# ETHERNET.net
KiCad netlist of a schematic drawn in Altium Designer
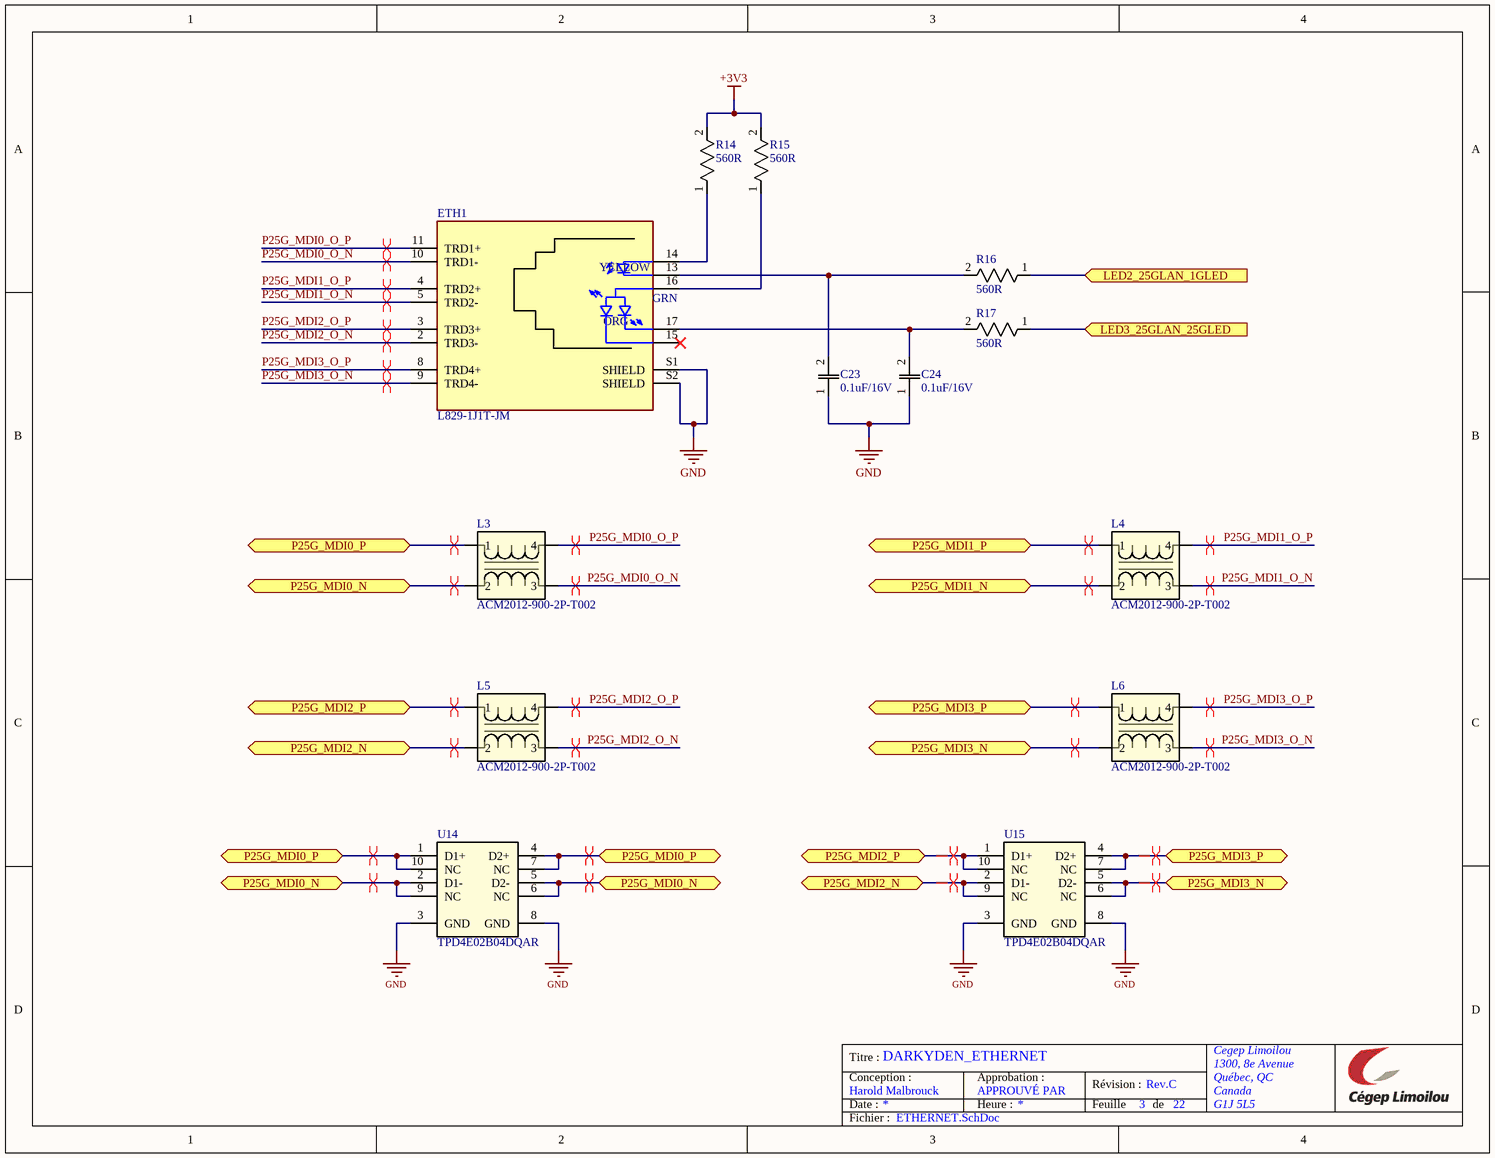
[diagram p0: ETHERNET.SchDoc]

(export (version "E")
  (design (tool "Eeschema 10.0.6"))
  (components
    (comp (ref "C23")
      (value "0.1uF/16V")
      (footprint "C0805")
      (description "0.1uF/16V ±10% X7R 0805 (2012METRIC) Ceramic Capacitor SMD Auto X7R")
      (fields
        (field (name "MANUFACTURER") "KEMET")
        (field (name "MANUFACTURER PART NUMBER") "C0805C104K4RACAUTO")
      )
      (libsource (lib "DARKYDEN") (part "C0805C104K4RACAUTO"))
    )
    (comp (ref "C24")
      (value "0.1uF/16V")
      (footprint "C0805")
      (description "0.1uF/16V ±10% X7R 0805 (2012METRIC) Ceramic Capacitor SMD Auto X7R")
      (fields
        (field (name "MANUFACTURER") "KEMET")
        (field (name "MANUFACTURER PART NUMBER") "C0805C104K4RACAUTO")
      )
      (libsource (lib "DARKYDEN") (part "C0805C104K4RACAUTO"))
    )
    (comp (ref "ETH1")
      (value "L829-1J1T-JM")
      (footprint "RJ-45")
      (description "Modular Connectors / Ethernet Connectors 1x1 2.5GBT MagJack")
      (fields
        (field (name "DIGI-KEY_PART_NUMBER") "507-2068-ND")
        (field (name "MF") "Bel Magnetic Solutions")
      )
      (libsource (lib "L829-1J1T-JM") (part "L829-1J1T-JM"))
    )
    (comp (ref "L3")
      (value "ACM2012-900-2P-T002")
      (footprint "SamacSys:ACM20129002PT002")
      (description "Ferrite Beads Wirewound Common Mode Filter 90Ohm 100MHz 400mA 0805 T/R")
      (fields (field (name "MOUSER PART NUMBER") "810-ACM20129002PT002") (field (name "MANUFACTURER") "TDK"))
      (libsource (lib "SamacSys") (part "ACM2012-900-2P-T002"))
    )
    (comp (ref "L4")
      (value "ACM2012-900-2P-T002")
      (footprint "SamacSys:ACM20129002PT002")
      (description "Ferrite Beads Wirewound Common Mode Filter 90Ohm 100MHz 400mA 0805 T/R")
      (fields (field (name "MOUSER PART NUMBER") "810-ACM20129002PT002") (field (name "MANUFACTURER") "TDK"))
      (libsource (lib "SamacSys") (part "ACM2012-900-2P-T002"))
    )
    (comp (ref "L5")
      (value "ACM2012-900-2P-T002")
      (footprint "SamacSys:ACM20129002PT002")
      (description "Ferrite Beads Wirewound Common Mode Filter 90Ohm 100MHz 400mA 0805 T/R")
      (fields (field (name "MOUSER PART NUMBER") "810-ACM20129002PT002") (field (name "MANUFACTURER") "TDK"))
      (libsource (lib "SamacSys") (part "ACM2012-900-2P-T002"))
    )
    (comp (ref "L6")
      (value "ACM2012-900-2P-T002")
      (footprint "SamacSys:ACM20129002PT002")
      (description "Ferrite Beads Wirewound Common Mode Filter 90Ohm 100MHz 400mA 0805 T/R")
      (fields (field (name "MOUSER PART NUMBER") "810-ACM20129002PT002") (field (name "MANUFACTURER") "TDK"))
      (libsource (lib "SamacSys") (part "ACM2012-900-2P-T002"))
    )
    (comp (ref "R14")
      (value "560R")
      (footprint "RESC1608X55N")
      (description "560 Ohm, ï¿½ 1%, 100 mW, 0603 [1608 Metric], Thick Film, Precision")
      (fields
        (field (name "MANUFACTURER") "Panasonic")
        (field (name "MANUFACTURER PART NUMBER") "ERJ-3EKF5600V")
      )
      (libsource (lib "DARKYDEN") (part "ERJ-3EKF5600V"))
    )
    (comp (ref "R15")
      (value "560R")
      (footprint "RESC1608X55N")
      (description "560 Ohm, ï¿½ 1%, 100 mW, 0603 [1608 Metric], Thick Film, Precision")
      (fields
        (field (name "MANUFACTURER") "Panasonic")
        (field (name "MANUFACTURER PART NUMBER") "ERJ-3EKF5600V")
      )
      (libsource (lib "DARKYDEN") (part "ERJ-3EKF5600V"))
    )
    (comp (ref "R16")
      (value "560R")
      (footprint "RESC1608X55N")
      (description "560 Ohm, ï¿½ 1%, 100 mW, 0603 [1608 Metric], Thick Film, Precision")
      (fields
        (field (name "MANUFACTURER") "Panasonic")
        (field (name "MANUFACTURER PART NUMBER") "ERJ-3EKF5600V")
      )
      (libsource (lib "DARKYDEN") (part "ERJ-3EKF5600V"))
    )
    (comp (ref "R17")
      (value "560R")
      (footprint "RESC1608X55N")
      (description "560 Ohm, ï¿½ 1%, 100 mW, 0603 [1608 Metric], Thick Film, Precision")
      (fields
        (field (name "MANUFACTURER") "Panasonic")
        (field (name "MANUFACTURER PART NUMBER") "ERJ-3EKF5600V")
      )
      (libsource (lib "DARKYDEN") (part "ERJ-3EKF5600V"))
    )
    (comp (ref "U14")
      (value "TPD4E02B04DQAR")
      (footprint "DQA0010A")
      (description "TVS DIODE 3.6V 8.8V 10USON / 4-Channel ESD Protection Diode for USB Type-C and HDMI 2.0")
      (fields (field (name "MANUFACTURER") "Texas Instruments"))
      (libsource (lib "TPD4E02B04DQAR") (part "TPD4E02B04DQAR"))
    )
    (comp (ref "U15")
      (value "TPD4E02B04DQAR")
      (footprint "DQA0010A")
      (description "TVS DIODE 3.6V 8.8V 10USON / 4-Channel ESD Protection Diode for USB Type-C and HDMI 2.0")
      (fields (field (name "MANUFACTURER") "Texas Instruments"))
      (libsource (lib "TPD4E02B04DQAR") (part "TPD4E02B04DQAR"))
    )
  )
  (nets
    (net (code "1") (name "+3V3") (class "Default")
      (node (ref "R14") (pin "2") (pinfunction "2_2") (pintype "passive"))
      (node (ref "R15") (pin "2") (pinfunction "2_2") (pintype "passive"))
    )
    (net (code "2") (name "/LED2_25GLAN_1GLED") (class "Default")
      (node (ref "R16") (pin "1") (pinfunction "1_1") (pintype "passive"))
    )
    (net (code "3") (name "/LED3_25GLAN_25GLED") (class "Default")
      (node (ref "R17") (pin "1") (pinfunction "1_1") (pintype "passive"))
    )
    (net (code "4") (name "/P25G_MDI0_N") (class "Default")
      (node (ref "L3") (pin "2") (pinfunction "2_2") (pintype "passive"))
      (node (ref "U14") (pin "2") (pinfunction "D1-_2") (pintype "passive"))
      (node (ref "U14") (pin "5") (pinfunction "D2-_5") (pintype "passive"))
      (node (ref "U14") (pin "6") (pinfunction "NC_6") (pintype "passive"))
      (node (ref "U14") (pin "9") (pinfunction "NC_9") (pintype "passive"))
    )
    (net (code "5") (name "/P25G_MDI0_O_N") (class "Default")
      (node (ref "ETH1") (pin "10") (pinfunction "TRD1-_10") (pintype "passive"))
      (node (ref "L3") (pin "3") (pinfunction "3_3") (pintype "passive"))
    )
    (net (code "6") (name "/P25G_MDI0_O_P") (class "Default")
      (node (ref "ETH1") (pin "11") (pinfunction "TRD1+_11") (pintype "passive"))
      (node (ref "L3") (pin "4") (pinfunction "4_4") (pintype "passive"))
    )
    (net (code "7") (name "/P25G_MDI0_P") (class "Default")
      (node (ref "L3") (pin "1") (pinfunction "1_1") (pintype "passive"))
      (node (ref "U14") (pin "1") (pinfunction "D1+_1") (pintype "passive"))
      (node (ref "U14") (pin "10") (pinfunction "NC_10") (pintype "passive"))
      (node (ref "U14") (pin "4") (pinfunction "D2+_4") (pintype "passive"))
      (node (ref "U14") (pin "7") (pinfunction "NC_7") (pintype "passive"))
    )
    (net (code "8") (name "/P25G_MDI1_N") (class "Default")
      (node (ref "L4") (pin "2") (pinfunction "2_2") (pintype "passive"))
    )
    (net (code "9") (name "/P25G_MDI1_O_N") (class "Default")
      (node (ref "ETH1") (pin "5") (pinfunction "TRD2-_5") (pintype "passive"))
      (node (ref "L4") (pin "3") (pinfunction "3_3") (pintype "passive"))
    )
    (net (code "10") (name "/P25G_MDI1_O_P") (class "Default")
      (node (ref "ETH1") (pin "4") (pinfunction "TRD2+_4") (pintype "passive"))
      (node (ref "L4") (pin "4") (pinfunction "4_4") (pintype "passive"))
    )
    (net (code "11") (name "/P25G_MDI1_P") (class "Default")
      (node (ref "L4") (pin "1") (pinfunction "1_1") (pintype "passive"))
    )
    (net (code "12") (name "/P25G_MDI2_N") (class "Default")
      (node (ref "L5") (pin "2") (pinfunction "2_2") (pintype "passive"))
      (node (ref "U15") (pin "2") (pinfunction "D1-_2") (pintype "passive"))
      (node (ref "U15") (pin "9") (pinfunction "NC_9") (pintype "passive"))
    )
    (net (code "13") (name "/P25G_MDI2_O_N") (class "Default")
      (node (ref "ETH1") (pin "2") (pinfunction "TRD3-_2") (pintype "passive"))
      (node (ref "L5") (pin "3") (pinfunction "3_3") (pintype "passive"))
    )
    (net (code "14") (name "/P25G_MDI2_O_P") (class "Default")
      (node (ref "ETH1") (pin "3") (pinfunction "TRD3+_3") (pintype "passive"))
      (node (ref "L5") (pin "4") (pinfunction "4_4") (pintype "passive"))
    )
    (net (code "15") (name "/P25G_MDI2_P") (class "Default")
      (node (ref "L5") (pin "1") (pinfunction "1_1") (pintype "passive"))
      (node (ref "U15") (pin "1") (pinfunction "D1+_1") (pintype "passive"))
      (node (ref "U15") (pin "10") (pinfunction "NC_10") (pintype "passive"))
    )
    (net (code "16") (name "/P25G_MDI3_N") (class "Default")
      (node (ref "L6") (pin "2") (pinfunction "2_2") (pintype "passive"))
      (node (ref "U15") (pin "5") (pinfunction "D2-_5") (pintype "passive"))
      (node (ref "U15") (pin "6") (pinfunction "NC_6") (pintype "passive"))
    )
    (net (code "17") (name "/P25G_MDI3_O_N") (class "Default")
      (node (ref "ETH1") (pin "9") (pinfunction "TRD4-_9") (pintype "passive"))
      (node (ref "L6") (pin "3") (pinfunction "3_3") (pintype "passive"))
    )
    (net (code "18") (name "/P25G_MDI3_O_P") (class "Default")
      (node (ref "ETH1") (pin "8") (pinfunction "TRD4+_8") (pintype "passive"))
      (node (ref "L6") (pin "4") (pinfunction "4_4") (pintype "passive"))
    )
    (net (code "19") (name "/P25G_MDI3_P") (class "Default")
      (node (ref "L6") (pin "1") (pinfunction "1_1") (pintype "passive"))
      (node (ref "U15") (pin "4") (pinfunction "D2+_4") (pintype "passive"))
      (node (ref "U15") (pin "7") (pinfunction "NC_7") (pintype "passive"))
    )
    (net (code "20") (name "GND") (class "Default")
      (node (ref "C23") (pin "1") (pinfunction "1_1") (pintype "passive"))
      (node (ref "C24") (pin "1") (pinfunction "1_1") (pintype "passive"))
      (node (ref "ETH1") (pin "S1") (pinfunction "SHIELD_S1") (pintype "passive"))
      (node (ref "ETH1") (pin "S2") (pinfunction "SHIELD_S2") (pintype "passive"))
      (node (ref "U14") (pin "3") (pinfunction "GND_3") (pintype "passive"))
      (node (ref "U14") (pin "8") (pinfunction "GND_8") (pintype "passive"))
      (node (ref "U15") (pin "3") (pinfunction "GND_3") (pintype "passive"))
      (node (ref "U15") (pin "8") (pinfunction "GND_8") (pintype "passive"))
    )
    (net (code "21") (name "Net-(ETH1-CA)") (class "Default")
      (node (ref "ETH1") (pin "16") (pinfunction "CA_16") (pintype "passive"))
      (node (ref "R15") (pin "1") (pinfunction "1_1") (pintype "passive"))
    )
    (net (code "22") (name "Net-(ETH1-GK_1)") (class "Default")
      (node (ref "C24") (pin "2") (pinfunction "2_2") (pintype "passive"))
      (node (ref "ETH1") (pin "17") (pinfunction "GK_1_17") (pintype "passive"))
      (node (ref "R17") (pin "2") (pinfunction "2_2") (pintype "passive"))
    )
    (net (code "23") (name "Net-(ETH1-YA_1)") (class "Default")
      (node (ref "ETH1") (pin "14") (pinfunction "YA_1_14") (pintype "passive"))
      (node (ref "R14") (pin "1") (pinfunction "1_1") (pintype "passive"))
    )
    (net (code "24") (name "Net-(ETH1-YK_1)") (class "Default")
      (node (ref "C23") (pin "2") (pinfunction "2_2") (pintype "passive"))
      (node (ref "ETH1") (pin "13") (pinfunction "YK_1_13") (pintype "passive"))
      (node (ref "R16") (pin "2") (pinfunction "2_2") (pintype "passive"))
    )
    (net (code "25") (name "unconnected-(ETH1-OK_1-Pad15)") (class "Default")
      (node (ref "ETH1") (pin "15") (pinfunction "OK_1_15") (pintype "passive+no_connect"))
    )
    (net (code "26") (name "unconnected-(ETH1-TRCT1-Pad12)") (class "Default")
      (node (ref "ETH1") (pin "12") (pinfunction "TRCT1_12") (pintype "passive"))
    )
    (net (code "27") (name "unconnected-(ETH1-TRCT2-Pad6)") (class "Default")
      (node (ref "ETH1") (pin "6") (pinfunction "TRCT2_6") (pintype "passive"))
    )
    (net (code "28") (name "unconnected-(ETH1-TRCT3-Pad1)") (class "Default")
      (node (ref "ETH1") (pin "1") (pinfunction "TRCT3_1") (pintype "passive"))
    )
    (net (code "29") (name "unconnected-(ETH1-TRCT4-Pad7)") (class "Default")
      (node (ref "ETH1") (pin "7") (pinfunction "TRCT4_7") (pintype "passive"))
    )
  )
)
